# circuito_visualizacion.net
KiCad netlist of a schematic drawn in EAGLE
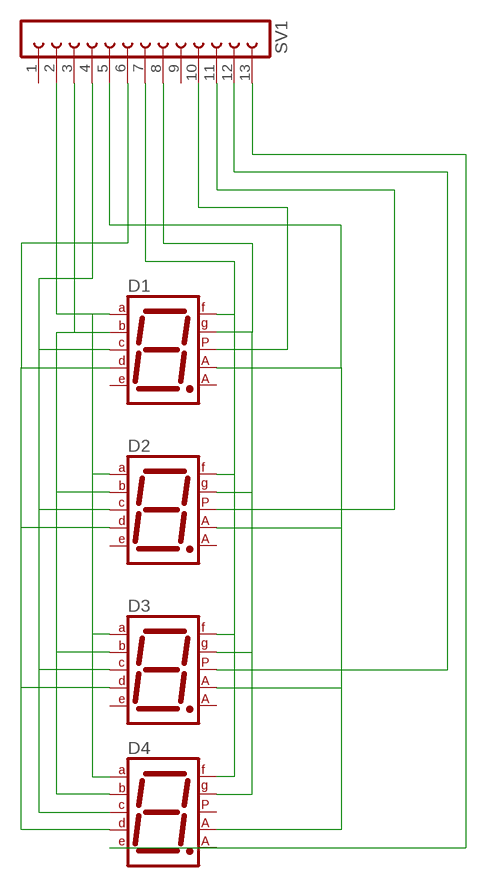
[diagram p0: schematic, sheet 1]

(export (version "E")
  (design (tool "Eeschema 10.0.6"))
  (components
    (comp (ref "D1")
      (value "7SEG-CA")
      (footprint "eagle-import:7SEG-13")
      (libsource (lib "eagle-import") (part "7SEG-CA"))
    )
    (comp (ref "D2")
      (value "7SEG-CA")
      (footprint "eagle-import:7SEG-13")
      (libsource (lib "eagle-import") (part "7SEG-CA"))
    )
    (comp (ref "D3")
      (value "7SEG-CA")
      (footprint "eagle-import:7SEG-13")
      (libsource (lib "eagle-import") (part "7SEG-CA"))
    )
    (comp (ref "D4")
      (value "7SEG-CA")
      (footprint "eagle-import:7SEG-13")
      (libsource (lib "eagle-import") (part "7SEG-CA"))
    )
    (comp (ref "SV1")
      (value "FE13-1")
      (footprint "eagle-import:FE13")
      (libsource (lib "eagle-import") (part "FE13-1"))
    )
  )
  (nets
    (net (code "1") (name "Net-(D1-A)") (class "Default")
      (node (ref "D1") (pin "7") (pinfunction "A_7") (pintype "passive"))
      (node (ref "D2") (pin "7") (pinfunction "A_7") (pintype "passive"))
      (node (ref "D3") (pin "7") (pinfunction "A_7") (pintype "passive"))
      (node (ref "D4") (pin "7") (pinfunction "A_7") (pintype "passive"))
      (node (ref "SV1") (pin "2") (pinfunction "2_2") (pintype "passive"))
    )
    (net (code "2") (name "Net-(D1-B)") (class "Default")
      (node (ref "D1") (pin "6") (pinfunction "B_6") (pintype "passive"))
      (node (ref "D2") (pin "6") (pinfunction "B_6") (pintype "passive"))
      (node (ref "D3") (pin "6") (pinfunction "B_6") (pintype "passive"))
      (node (ref "D4") (pin "6") (pinfunction "B_6") (pintype "passive"))
      (node (ref "SV1") (pin "3") (pinfunction "3_3") (pintype "passive"))
    )
    (net (code "3") (name "Net-(D1-C)") (class "Default")
      (node (ref "D1") (pin "4") (pinfunction "C_4") (pintype "passive"))
      (node (ref "D2") (pin "4") (pinfunction "C_4") (pintype "passive"))
      (node (ref "D3") (pin "4") (pinfunction "C_4") (pintype "passive"))
      (node (ref "D4") (pin "4") (pinfunction "C_4") (pintype "passive"))
      (node (ref "SV1") (pin "4") (pinfunction "4_4") (pintype "passive"))
    )
    (net (code "4") (name "Net-(D1-CA1)") (class "Default")
      (node (ref "D1") (pin "3") (pinfunction "CA1_3") (pintype "passive"))
      (node (ref "D2") (pin "3") (pinfunction "CA1_3") (pintype "passive"))
      (node (ref "D3") (pin "3") (pinfunction "CA1_3") (pintype "passive"))
      (node (ref "D4") (pin "3") (pinfunction "CA1_3") (pintype "passive"))
      (node (ref "SV1") (pin "5") (pinfunction "5_5") (pintype "passive"))
    )
    (net (code "5") (name "Net-(D1-D)") (class "Default")
      (node (ref "D1") (pin "2") (pinfunction "D_2") (pintype "passive"))
      (node (ref "D2") (pin "2") (pinfunction "D_2") (pintype "passive"))
      (node (ref "D3") (pin "2") (pinfunction "D_2") (pintype "passive"))
      (node (ref "D4") (pin "2") (pinfunction "D_2") (pintype "passive"))
      (node (ref "SV1") (pin "6") (pinfunction "6_6") (pintype "passive"))
    )
    (net (code "6") (name "Net-(D1-DP)") (class "Default")
      (node (ref "D1") (pin "5") (pinfunction "DP_5") (pintype "passive"))
      (node (ref "SV1") (pin "10") (pinfunction "10_10") (pintype "passive"))
    )
    (net (code "7") (name "Net-(D1-F)") (class "Default")
      (node (ref "D1") (pin "9") (pinfunction "F_9") (pintype "passive"))
      (node (ref "D2") (pin "9") (pinfunction "F_9") (pintype "passive"))
      (node (ref "D3") (pin "9") (pinfunction "F_9") (pintype "passive"))
      (node (ref "D4") (pin "9") (pinfunction "F_9") (pintype "passive"))
      (node (ref "SV1") (pin "7") (pinfunction "7_7") (pintype "passive"))
    )
    (net (code "8") (name "Net-(D1-G)") (class "Default")
      (node (ref "D1") (pin "10") (pinfunction "G_10") (pintype "passive"))
      (node (ref "D2") (pin "10") (pinfunction "G_10") (pintype "passive"))
      (node (ref "D3") (pin "10") (pinfunction "G_10") (pintype "passive"))
      (node (ref "D4") (pin "10") (pinfunction "G_10") (pintype "passive"))
      (node (ref "SV1") (pin "8") (pinfunction "8_8") (pintype "passive"))
    )
    (net (code "9") (name "Net-(D2-DP)") (class "Default")
      (node (ref "D2") (pin "5") (pinfunction "DP_5") (pintype "passive"))
      (node (ref "SV1") (pin "11") (pinfunction "11_11") (pintype "passive"))
    )
    (net (code "10") (name "Net-(D3-DP)") (class "Default")
      (node (ref "D3") (pin "5") (pinfunction "DP_5") (pintype "passive"))
      (node (ref "SV1") (pin "12") (pinfunction "12_12") (pintype "passive"))
    )
    (net (code "11") (name "Net-(D4-E)") (class "Default")
      (node (ref "D4") (pin "1") (pinfunction "E_1") (pintype "passive"))
      (node (ref "SV1") (pin "13") (pinfunction "13_13") (pintype "passive"))
    )
    (net (code "12") (name "unconnected-(D1-CA2-Pad8)") (class "Default")
      (node (ref "D1") (pin "8") (pinfunction "CA2_8") (pintype "passive"))
    )
    (net (code "13") (name "unconnected-(D1-E-Pad1)") (class "Default")
      (node (ref "D1") (pin "1") (pinfunction "E_1") (pintype "passive"))
    )
    (net (code "14") (name "unconnected-(D2-CA2-Pad8)") (class "Default")
      (node (ref "D2") (pin "8") (pinfunction "CA2_8") (pintype "passive"))
    )
    (net (code "15") (name "unconnected-(D2-E-Pad1)") (class "Default")
      (node (ref "D2") (pin "1") (pinfunction "E_1") (pintype "passive"))
    )
    (net (code "16") (name "unconnected-(D3-CA2-Pad8)") (class "Default")
      (node (ref "D3") (pin "8") (pinfunction "CA2_8") (pintype "passive"))
    )
    (net (code "17") (name "unconnected-(D3-E-Pad1)") (class "Default")
      (node (ref "D3") (pin "1") (pinfunction "E_1") (pintype "passive"))
    )
    (net (code "18") (name "unconnected-(D4-CA2-Pad8)") (class "Default")
      (node (ref "D4") (pin "8") (pinfunction "CA2_8") (pintype "passive"))
    )
    (net (code "19") (name "unconnected-(D4-DP-Pad5)") (class "Default")
      (node (ref "D4") (pin "5") (pinfunction "DP_5") (pintype "passive"))
    )
    (net (code "20") (name "unconnected-(SV1-Pad1)") (class "Default")
      (node (ref "SV1") (pin "1") (pinfunction "1_1") (pintype "passive"))
    )
    (net (code "21") (name "unconnected-(SV1-Pad9)") (class "Default")
      (node (ref "SV1") (pin "9") (pinfunction "9_9") (pintype "passive"))
    )
  )
)
